# Remote.net
KiCad netlist of a schematic drawn in EAGLE
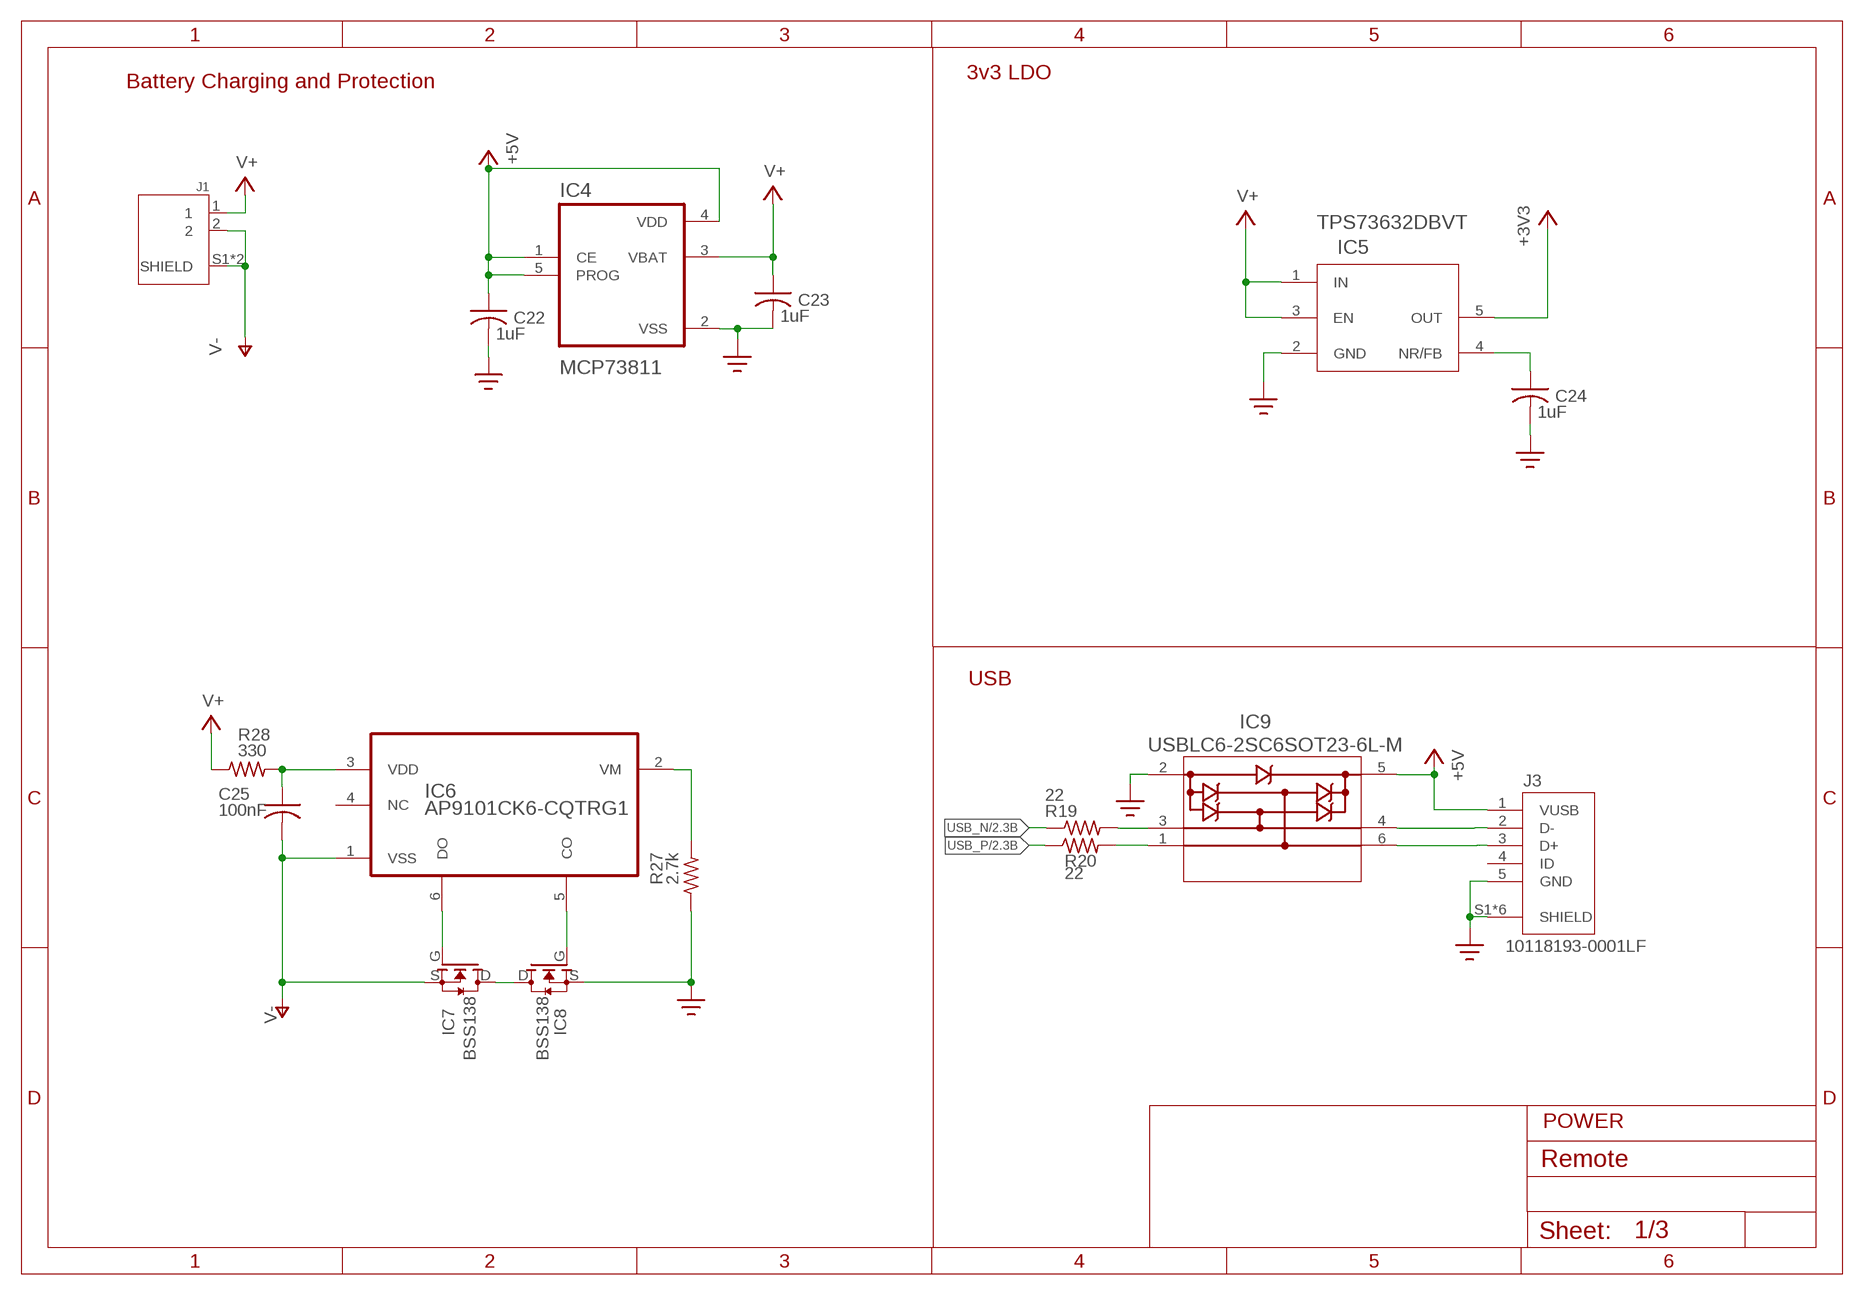
[diagram p0: schematic, sheet 1]
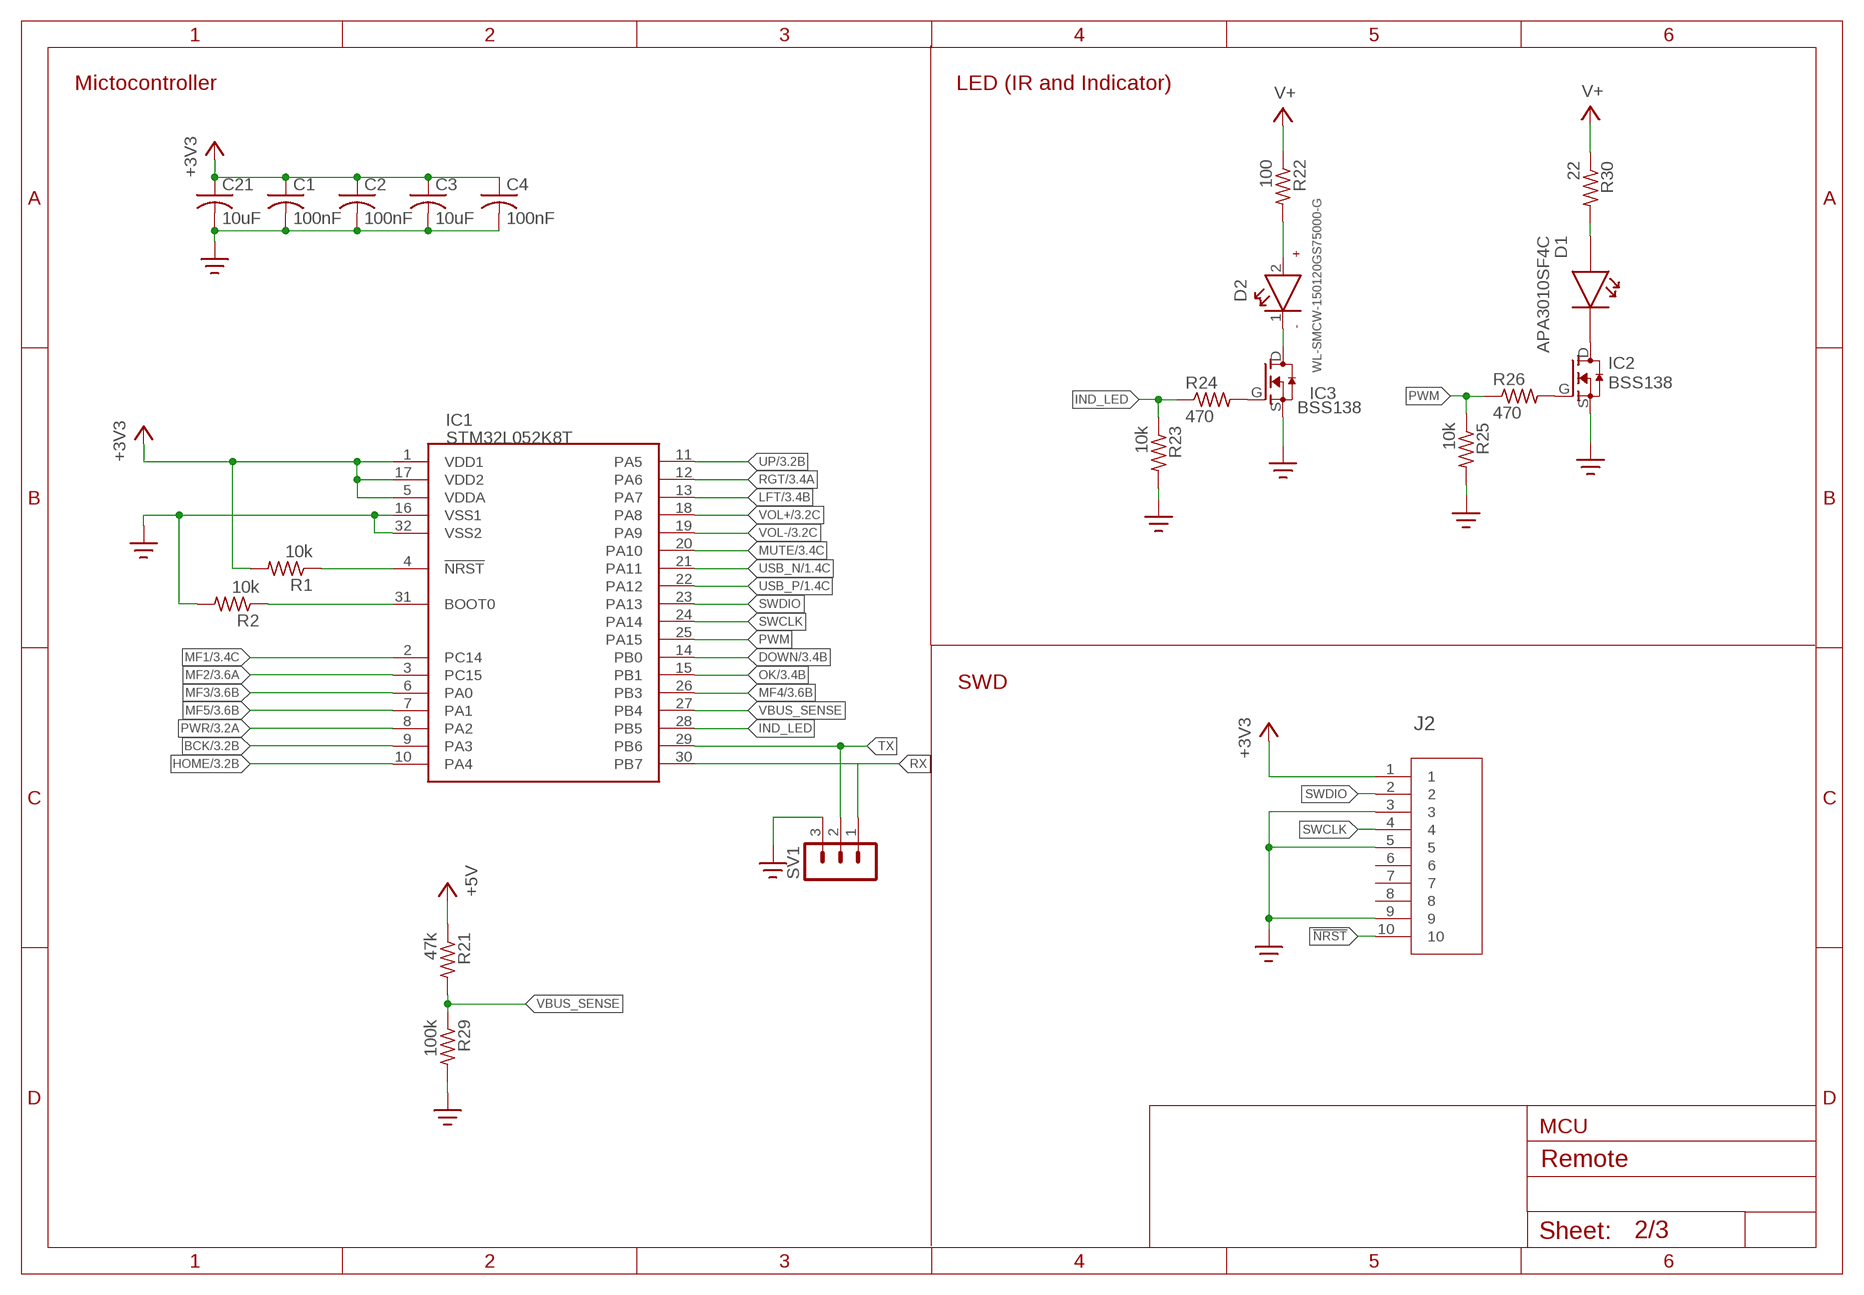
[diagram p1: schematic, sheet 2]
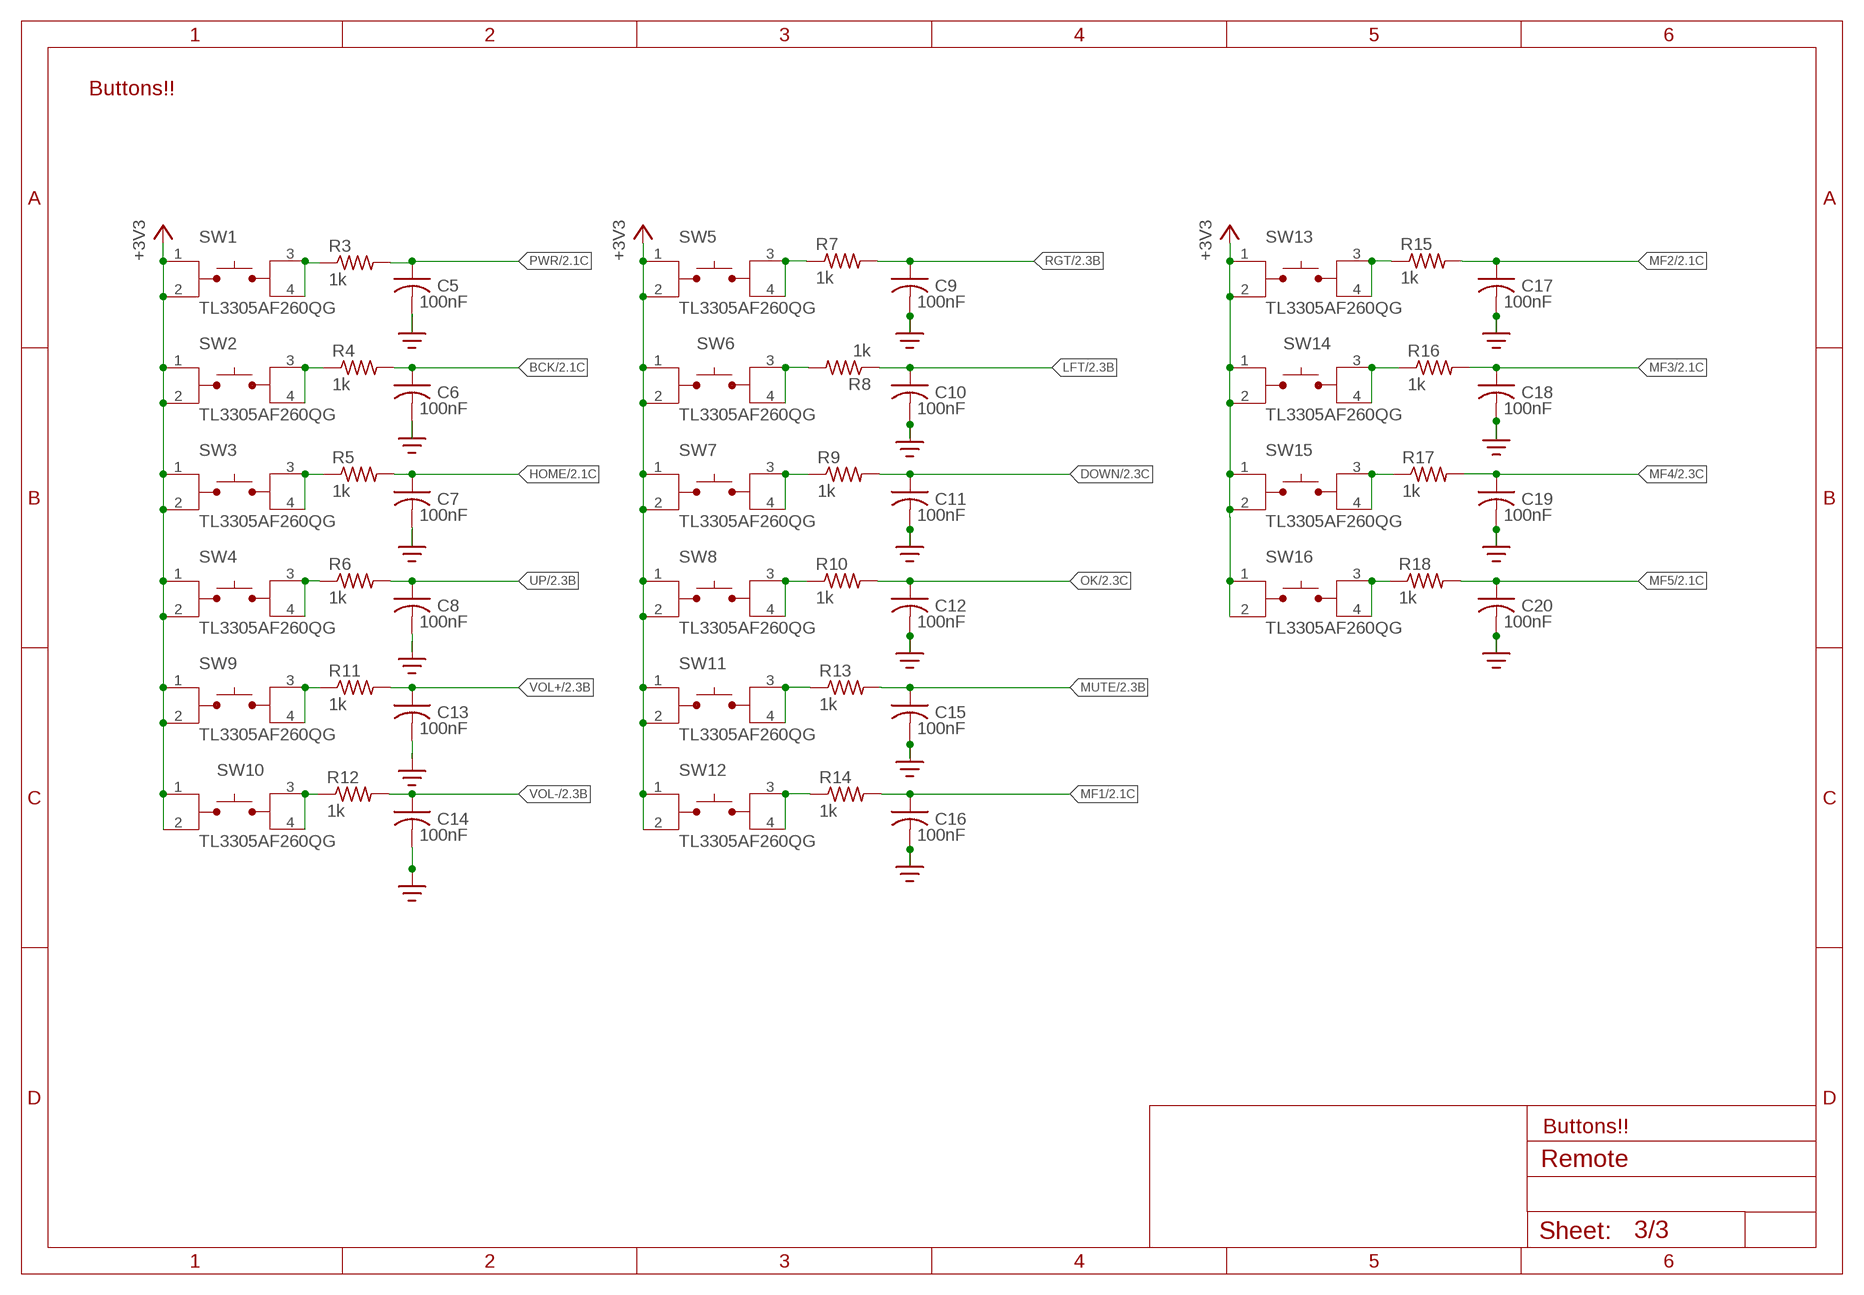
[diagram p2: schematic, sheet 3]

(export (version "E")
  (design (tool "Eeschema 10.0.6"))
  (components
    (comp (ref "C5")
      (value "100nF")
      (footprint "eagle-import:C0805K")
      (libsource (lib "eagle-import") (part "C-USC0805K"))
    )
    (comp (ref "C6")
      (value "100nF")
      (footprint "eagle-import:C0805K")
      (libsource (lib "eagle-import") (part "C-USC0805K"))
    )
    (comp (ref "C7")
      (value "100nF")
      (footprint "eagle-import:C0805K")
      (libsource (lib "eagle-import") (part "C-USC0805K"))
    )
    (comp (ref "C8")
      (value "100nF")
      (footprint "eagle-import:C0805K")
      (libsource (lib "eagle-import") (part "C-USC0805K"))
    )
    (comp (ref "C9")
      (value "100nF")
      (footprint "eagle-import:C0805K")
      (libsource (lib "eagle-import") (part "C-USC0805K"))
    )
    (comp (ref "C10")
      (value "100nF")
      (footprint "eagle-import:C0805K")
      (libsource (lib "eagle-import") (part "C-USC0805K"))
    )
    (comp (ref "C11")
      (value "100nF")
      (footprint "eagle-import:C0805K")
      (libsource (lib "eagle-import") (part "C-USC0805K"))
    )
    (comp (ref "C12")
      (value "100nF")
      (footprint "eagle-import:C0805K")
      (libsource (lib "eagle-import") (part "C-USC0805K"))
    )
    (comp (ref "C13")
      (value "100nF")
      (footprint "eagle-import:C0805K")
      (libsource (lib "eagle-import") (part "C-USC0805K"))
    )
    (comp (ref "C14")
      (value "100nF")
      (footprint "eagle-import:C0805K")
      (libsource (lib "eagle-import") (part "C-USC0805K"))
    )
    (comp (ref "C15")
      (value "100nF")
      (footprint "eagle-import:C0805K")
      (libsource (lib "eagle-import") (part "C-USC0805K"))
    )
    (comp (ref "C16")
      (value "100nF")
      (footprint "eagle-import:C0805K")
      (libsource (lib "eagle-import") (part "C-USC0805K"))
    )
    (comp (ref "C17")
      (value "100nF")
      (footprint "eagle-import:C0805K")
      (libsource (lib "eagle-import") (part "C-USC0805K"))
    )
    (comp (ref "C18")
      (value "100nF")
      (footprint "eagle-import:C0805K")
      (libsource (lib "eagle-import") (part "C-USC0805K"))
    )
    (comp (ref "C19")
      (value "100nF")
      (footprint "eagle-import:C0805K")
      (libsource (lib "eagle-import") (part "C-USC0805K"))
    )
    (comp (ref "C20")
      (value "100nF")
      (footprint "eagle-import:C0805K")
      (libsource (lib "eagle-import") (part "C-USC0805K"))
    )
    (comp (ref "R3")
      (value "1k")
      (footprint "eagle-import:R0805W")
      (libsource (lib "eagle-import") (part "R-US_R0805W"))
    )
    (comp (ref "R4")
      (value "1k")
      (footprint "eagle-import:R0805W")
      (libsource (lib "eagle-import") (part "R-US_R0805W"))
    )
    (comp (ref "R5")
      (value "1k")
      (footprint "eagle-import:R0805W")
      (libsource (lib "eagle-import") (part "R-US_R0805W"))
    )
    (comp (ref "R6")
      (value "1k")
      (footprint "eagle-import:R0805W")
      (libsource (lib "eagle-import") (part "R-US_R0805W"))
    )
    (comp (ref "R7")
      (value "1k")
      (footprint "eagle-import:R0805W")
      (libsource (lib "eagle-import") (part "R-US_R0805W"))
    )
    (comp (ref "R8")
      (value "1k")
      (footprint "eagle-import:R0805W")
      (libsource (lib "eagle-import") (part "R-US_R0805W"))
    )
    (comp (ref "R9")
      (value "1k")
      (footprint "eagle-import:R0805W")
      (libsource (lib "eagle-import") (part "R-US_R0805W"))
    )
    (comp (ref "R10")
      (value "1k")
      (footprint "eagle-import:R0805W")
      (libsource (lib "eagle-import") (part "R-US_R0805W"))
    )
    (comp (ref "R11")
      (value "1k")
      (footprint "eagle-import:R0805W")
      (libsource (lib "eagle-import") (part "R-US_R0805W"))
    )
    (comp (ref "R12")
      (value "1k")
      (footprint "eagle-import:R0805W")
      (libsource (lib "eagle-import") (part "R-US_R0805W"))
    )
    (comp (ref "R13")
      (value "1k")
      (footprint "eagle-import:R0805W")
      (libsource (lib "eagle-import") (part "R-US_R0805W"))
    )
    (comp (ref "R14")
      (value "1k")
      (footprint "eagle-import:R0805W")
      (libsource (lib "eagle-import") (part "R-US_R0805W"))
    )
    (comp (ref "R15")
      (value "1k")
      (footprint "eagle-import:R0805W")
      (libsource (lib "eagle-import") (part "R-US_R0805W"))
    )
    (comp (ref "R16")
      (value "1k")
      (footprint "eagle-import:R0805W")
      (libsource (lib "eagle-import") (part "R-US_R0805W"))
    )
    (comp (ref "R17")
      (value "1k")
      (footprint "eagle-import:R0805W")
      (libsource (lib "eagle-import") (part "R-US_R0805W"))
    )
    (comp (ref "R18")
      (value "1k")
      (footprint "eagle-import:R0805W")
      (libsource (lib "eagle-import") (part "R-US_R0805W"))
    )
    (comp (ref "SW1")
      (value "TL3305AF260QG")
      (footprint "eagle-import:SW_TL3305AF260QG")
      (fields (field (name "DIGI-KEY_PART_NUMBER") "EG5353CT-ND") (field (name "MF") "E-Switch"))
      (libsource (lib "eagle-import") (part "TL3305AF260QG"))
    )
    (comp (ref "SW2")
      (value "TL3305AF260QG")
      (footprint "eagle-import:SW_TL3305AF260QG")
      (fields (field (name "DIGI-KEY_PART_NUMBER") "EG5353CT-ND") (field (name "MF") "E-Switch"))
      (libsource (lib "eagle-import") (part "TL3305AF260QG"))
    )
    (comp (ref "SW3")
      (value "TL3305AF260QG")
      (footprint "eagle-import:SW_TL3305AF260QG")
      (fields (field (name "DIGI-KEY_PART_NUMBER") "EG5353CT-ND") (field (name "MF") "E-Switch"))
      (libsource (lib "eagle-import") (part "TL3305AF260QG"))
    )
    (comp (ref "SW4")
      (value "TL3305AF260QG")
      (footprint "eagle-import:SW_TL3305AF260QG")
      (fields (field (name "DIGI-KEY_PART_NUMBER") "EG5353CT-ND") (field (name "MF") "E-Switch"))
      (libsource (lib "eagle-import") (part "TL3305AF260QG"))
    )
    (comp (ref "SW5")
      (value "TL3305AF260QG")
      (footprint "eagle-import:SW_TL3305AF260QG")
      (fields (field (name "DIGI-KEY_PART_NUMBER") "EG5353CT-ND") (field (name "MF") "E-Switch"))
      (libsource (lib "eagle-import") (part "TL3305AF260QG"))
    )
    (comp (ref "SW6")
      (value "TL3305AF260QG")
      (footprint "eagle-import:SW_TL3305AF260QG")
      (fields (field (name "DIGI-KEY_PART_NUMBER") "EG5353CT-ND") (field (name "MF") "E-Switch"))
      (libsource (lib "eagle-import") (part "TL3305AF260QG"))
    )
    (comp (ref "SW7")
      (value "TL3305AF260QG")
      (footprint "eagle-import:SW_TL3305AF260QG")
      (fields (field (name "DIGI-KEY_PART_NUMBER") "EG5353CT-ND") (field (name "MF") "E-Switch"))
      (libsource (lib "eagle-import") (part "TL3305AF260QG"))
    )
    (comp (ref "SW8")
      (value "TL3305AF260QG")
      (footprint "eagle-import:SW_TL3305AF260QG")
      (fields (field (name "DIGI-KEY_PART_NUMBER") "EG5353CT-ND") (field (name "MF") "E-Switch"))
      (libsource (lib "eagle-import") (part "TL3305AF260QG"))
    )
    (comp (ref "SW9")
      (value "TL3305AF260QG")
      (footprint "eagle-import:SW_TL3305AF260QG")
      (fields (field (name "DIGI-KEY_PART_NUMBER") "EG5353CT-ND") (field (name "MF") "E-Switch"))
      (libsource (lib "eagle-import") (part "TL3305AF260QG"))
    )
    (comp (ref "SW10")
      (value "TL3305AF260QG")
      (footprint "eagle-import:SW_TL3305AF260QG")
      (fields (field (name "DIGI-KEY_PART_NUMBER") "EG5353CT-ND") (field (name "MF") "E-Switch"))
      (libsource (lib "eagle-import") (part "TL3305AF260QG"))
    )
    (comp (ref "SW11")
      (value "TL3305AF260QG")
      (footprint "eagle-import:SW_TL3305AF260QG")
      (fields (field (name "DIGI-KEY_PART_NUMBER") "EG5353CT-ND") (field (name "MF") "E-Switch"))
      (libsource (lib "eagle-import") (part "TL3305AF260QG"))
    )
    (comp (ref "SW12")
      (value "TL3305AF260QG")
      (footprint "eagle-import:SW_TL3305AF260QG")
      (fields (field (name "DIGI-KEY_PART_NUMBER") "EG5353CT-ND") (field (name "MF") "E-Switch"))
      (libsource (lib "eagle-import") (part "TL3305AF260QG"))
    )
    (comp (ref "SW13")
      (value "TL3305AF260QG")
      (footprint "eagle-import:SW_TL3305AF260QG")
      (fields (field (name "DIGI-KEY_PART_NUMBER") "EG5353CT-ND") (field (name "MF") "E-Switch"))
      (libsource (lib "eagle-import") (part "TL3305AF260QG"))
    )
    (comp (ref "SW14")
      (value "TL3305AF260QG")
      (footprint "eagle-import:SW_TL3305AF260QG")
      (fields (field (name "DIGI-KEY_PART_NUMBER") "EG5353CT-ND") (field (name "MF") "E-Switch"))
      (libsource (lib "eagle-import") (part "TL3305AF260QG"))
    )
    (comp (ref "SW15")
      (value "TL3305AF260QG")
      (footprint "eagle-import:SW_TL3305AF260QG")
      (fields (field (name "DIGI-KEY_PART_NUMBER") "EG5353CT-ND") (field (name "MF") "E-Switch"))
      (libsource (lib "eagle-import") (part "TL3305AF260QG"))
    )
    (comp (ref "SW16")
      (value "TL3305AF260QG")
      (footprint "eagle-import:SW_TL3305AF260QG")
      (fields (field (name "DIGI-KEY_PART_NUMBER") "EG5353CT-ND") (field (name "MF") "E-Switch"))
      (libsource (lib "eagle-import") (part "TL3305AF260QG"))
    )
    (comp (ref "C1")
      (value "100nF")
      (footprint "eagle-import:C0805K")
      (libsource (lib "eagle-import") (part "C-USC0805K"))
    )
    (comp (ref "C2")
      (value "100nF")
      (footprint "eagle-import:C0805K")
      (libsource (lib "eagle-import") (part "C-USC0805K"))
    )
    (comp (ref "C3")
      (value "10uF")
      (footprint "eagle-import:C0805K")
      (libsource (lib "eagle-import") (part "C-USC0805K"))
    )
    (comp (ref "C4")
      (value "100nF")
      (footprint "eagle-import:C0805K")
      (libsource (lib "eagle-import") (part "C-USC0805K"))
    )
    (comp (ref "C21")
      (value "10uF")
      (footprint "eagle-import:C0805K")
      (libsource (lib "eagle-import") (part "C-USC0805K"))
    )
    (comp (ref "D1")
      (value "APA3010SF4C")
      (footprint "eagle-import:APA3010SF4C")
      (fields (field (name "DIGI-KEY_PART_NUMBER") "754-1070-1-ND") (field (name "MF") "Kingbright"))
      (libsource (lib "eagle-import") (part "APA3010SF4C"))
    )
    (comp (ref "D2")
      (value "WL-SMCW-150120GS75000-G")
      (footprint "eagle-import:WL-SMCW_1206")
      (fields (field (name "MF") "Wurth Electronics") (field (name "MP") "150060VS75000"))
      (libsource (lib "eagle-import") (part "WL-SMCW-150120GS75000-G"))
    )
    (comp (ref "IC1")
      (value "STM32L052K8T")
      (footprint "eagle-import:QFP80P900X900X160-32N")
      (libsource (lib "eagle-import") (part "STM32L052K8T"))
    )
    (comp (ref "IC2")
      (value "BSS138")
      (footprint "eagle-import:BSS138")
      (fields (field (name "MF") "MICROSS/On Semiconductor"))
      (libsource (lib "eagle-import") (part "BSS138"))
    )
    (comp (ref "IC3")
      (value "BSS138")
      (footprint "eagle-import:BSS138")
      (fields (field (name "MF") "MICROSS/On Semiconductor"))
      (libsource (lib "eagle-import") (part "BSS138"))
    )
    (comp (ref "J2")
      (value "20021121-00010C4LF")
      (footprint "eagle-import:CONN_00010C4LF_AMP")
      (fields (field (name "COPYRIGHT") "Copyright (C) 2018 Accelerated Designs. All rights reserved"))
      (libsource (lib "eagle-import") (part "20021121-00010C4LF"))
    )
    (comp (ref "R1")
      (value "10k")
      (footprint "eagle-import:R0805W")
      (libsource (lib "eagle-import") (part "R-US_R0805W"))
    )
    (comp (ref "R2")
      (value "10k")
      (footprint "eagle-import:R0805W")
      (libsource (lib "eagle-import") (part "R-US_R0805W"))
    )
    (comp (ref "R21")
      (value "47k")
      (footprint "eagle-import:R0805W")
      (libsource (lib "eagle-import") (part "R-US_R0805W"))
    )
    (comp (ref "R22")
      (value "100")
      (footprint "eagle-import:R0805W")
      (libsource (lib "eagle-import") (part "R-US_R0805W"))
    )
    (comp (ref "R23")
      (value "10k")
      (footprint "eagle-import:R0805W")
      (libsource (lib "eagle-import") (part "R-US_R0805W"))
    )
    (comp (ref "R24")
      (value "470")
      (footprint "eagle-import:R0805W")
      (libsource (lib "eagle-import") (part "R-US_R0805W"))
    )
    (comp (ref "R25")
      (value "10k")
      (footprint "eagle-import:R0805W")
      (libsource (lib "eagle-import") (part "R-US_R0805W"))
    )
    (comp (ref "R26")
      (value "470")
      (footprint "eagle-import:R0805W")
      (libsource (lib "eagle-import") (part "R-US_R0805W"))
    )
    (comp (ref "R29")
      (value "100k")
      (footprint "eagle-import:R0805W")
      (libsource (lib "eagle-import") (part "R-US_R0805W"))
    )
    (comp (ref "R30")
      (value "22")
      (footprint "eagle-import:R0805W")
      (libsource (lib "eagle-import") (part "R-US_R0805W"))
    )
    (comp (ref "SV1")
      (value "MA03-1")
      (footprint "eagle-import:MA03-1")
      (libsource (lib "eagle-import") (part "MA03-1"))
    )
    (comp (ref "C22")
      (value "1uF")
      (footprint "eagle-import:C0805K")
      (libsource (lib "eagle-import") (part "C-USC0805K"))
    )
    (comp (ref "C23")
      (value "1uF")
      (footprint "eagle-import:C0805K")
      (libsource (lib "eagle-import") (part "C-USC0805K"))
    )
    (comp (ref "C24")
      (value "1uF")
      (footprint "eagle-import:C0805K")
      (libsource (lib "eagle-import") (part "C-USC0805K"))
    )
    (comp (ref "C25")
      (value "100nF")
      (footprint "eagle-import:C0805K")
      (libsource (lib "eagle-import") (part "C-USC0805K"))
    )
    (comp (ref "IC4")
      (value "MCP73811")
      (footprint "eagle-import:SOT95P280X145-5N")
      (fields
        (field (name "DIGI-KEY_PART_NUMBER") "MCP73811T-420I/OTCT-ND")
        (field (name "MF") "Microchip")
        (field (name "MP") "MCP73811T-420I/OT")
      )
      (libsource (lib "eagle-import") (part "MCP73811T-420I/OT"))
    )
    (comp (ref "IC5")
      (value "TPS73632DBVT")
      (footprint "eagle-import:DBV5-M")
      (fields (field (name "MANUFACTURER") "Texas Instruments"))
      (libsource (lib "eagle-import") (part "TPS73632DBVTDBV5-M"))
    )
    (comp (ref "IC6")
      (value "AP9101CK6-CQTRG1")
      (footprint "eagle-import:SOT95P280X140-6N")
      (fields (field (name "MF") "Diodes Inc."))
      (libsource (lib "eagle-import") (part "AP9101CK6-CQTRG1"))
    )
    (comp (ref "IC7")
      (value "BSS138")
      (footprint "eagle-import:BSS138")
      (fields (field (name "MF") "MICROSS/On Semiconductor"))
      (libsource (lib "eagle-import") (part "BSS138"))
    )
    (comp (ref "IC8")
      (value "BSS138")
      (footprint "eagle-import:BSS138")
      (fields (field (name "MF") "MICROSS/On Semiconductor"))
      (libsource (lib "eagle-import") (part "BSS138"))
    )
    (comp (ref "IC9")
      (value "USBLC6-2SC6SOT23-6L-M")
      (footprint "eagle-import:SOT23-6L-M")
      (fields (field (name "MANUFACTURER_PART_NUMBER") "USBLC6-2SC6"))
      (libsource (lib "eagle-import") (part "USBLC6-2SC6SOT23-6L-M"))
    )
    (comp (ref "J1")
      (value "S2B-PH-SM4-TB(LF)(SN)")
      (footprint "eagle-import:JST_S2B-PH-SM4-TB(LF)(SN)")
      (fields (field (name "MF") "JST Sales") (field (name "MP") "S2B-PH-SM4-TB_LF__SN_"))
      (libsource (lib "eagle-import") (part "S2B-PH-SM4-TB(LF)(SN)"))
    )
    (comp (ref "J3")
      (value "10118193-0001LF")
      (footprint "eagle-import:FCI_10118193-0001LF")
      (fields (field (name "DIGI-KEY_PART_NUMBER") "609-4616-1-ND") (field (name "MF") "Amphenol ICC"))
      (libsource (lib "eagle-import") (part "10118193-0001LF"))
    )
    (comp (ref "R19")
      (value "22")
      (footprint "eagle-import:R0805W")
      (libsource (lib "eagle-import") (part "R-US_R0805W"))
    )
    (comp (ref "R20")
      (value "22")
      (footprint "eagle-import:R0805W")
      (libsource (lib "eagle-import") (part "R-US_R0805W"))
    )
    (comp (ref "R27")
      (value "2.7k")
      (footprint "eagle-import:R0805W")
      (libsource (lib "eagle-import") (part "R-US_R0805W"))
    )
    (comp (ref "R28")
      (value "330")
      (footprint "eagle-import:R0805W")
      (libsource (lib "eagle-import") (part "R-US_R0805W"))
    )
  )
  (nets
    (net (code "1") (name "+3V3") (class "Default")
      (node (ref "C1") (pin "1") (pinfunction "1_1") (pintype "passive"))
      (node (ref "C2") (pin "1") (pinfunction "1_1") (pintype "passive"))
      (node (ref "C21") (pin "1") (pinfunction "1_1") (pintype "passive"))
      (node (ref "C3") (pin "1") (pinfunction "1_1") (pintype "passive"))
      (node (ref "C4") (pin "1") (pinfunction "1_1") (pintype "passive"))
      (node (ref "IC1") (pin "1") (pinfunction "VDD1_1") (pintype "power_in"))
      (node (ref "IC1") (pin "17") (pinfunction "VDD2_17") (pintype "power_in"))
      (node (ref "IC1") (pin "5") (pinfunction "VDDA_5") (pintype "power_in"))
      (node (ref "IC5") (pin "5") (pinfunction "OUT_5") (pintype "output"))
      (node (ref "J2") (pin "1") (pinfunction "1_1") (pintype "passive"))
      (node (ref "R1") (pin "2") (pinfunction "2_2") (pintype "passive"))
      (node (ref "SW1") (pin "1") (pinfunction "1_1") (pintype "passive"))
      (node (ref "SW1") (pin "2") (pinfunction "2_2") (pintype "passive"))
      (node (ref "SW10") (pin "1") (pinfunction "1_1") (pintype "passive"))
      (node (ref "SW10") (pin "2") (pinfunction "2_2") (pintype "passive"))
      (node (ref "SW11") (pin "1") (pinfunction "1_1") (pintype "passive"))
      (node (ref "SW11") (pin "2") (pinfunction "2_2") (pintype "passive"))
      (node (ref "SW12") (pin "1") (pinfunction "1_1") (pintype "passive"))
      (node (ref "SW12") (pin "2") (pinfunction "2_2") (pintype "passive"))
      (node (ref "SW13") (pin "1") (pinfunction "1_1") (pintype "passive"))
      (node (ref "SW13") (pin "2") (pinfunction "2_2") (pintype "passive"))
      (node (ref "SW14") (pin "1") (pinfunction "1_1") (pintype "passive"))
      (node (ref "SW14") (pin "2") (pinfunction "2_2") (pintype "passive"))
      (node (ref "SW15") (pin "1") (pinfunction "1_1") (pintype "passive"))
      (node (ref "SW15") (pin "2") (pinfunction "2_2") (pintype "passive"))
      (node (ref "SW16") (pin "1") (pinfunction "1_1") (pintype "passive"))
      (node (ref "SW16") (pin "2") (pinfunction "2_2") (pintype "passive"))
      (node (ref "SW2") (pin "1") (pinfunction "1_1") (pintype "passive"))
      (node (ref "SW2") (pin "2") (pinfunction "2_2") (pintype "passive"))
      (node (ref "SW3") (pin "1") (pinfunction "1_1") (pintype "passive"))
      (node (ref "SW3") (pin "2") (pinfunction "2_2") (pintype "passive"))
      (node (ref "SW4") (pin "1") (pinfunction "1_1") (pintype "passive"))
      (node (ref "SW4") (pin "2") (pinfunction "2_2") (pintype "passive"))
      (node (ref "SW5") (pin "1") (pinfunction "1_1") (pintype "passive"))
      (node (ref "SW5") (pin "2") (pinfunction "2_2") (pintype "passive"))
      (node (ref "SW6") (pin "1") (pinfunction "1_1") (pintype "passive"))
      (node (ref "SW6") (pin "2") (pinfunction "2_2") (pintype "passive"))
      (node (ref "SW7") (pin "1") (pinfunction "1_1") (pintype "passive"))
      (node (ref "SW7") (pin "2") (pinfunction "2_2") (pintype "passive"))
      (node (ref "SW8") (pin "1") (pinfunction "1_1") (pintype "passive"))
      (node (ref "SW8") (pin "2") (pinfunction "2_2") (pintype "passive"))
      (node (ref "SW9") (pin "1") (pinfunction "1_1") (pintype "passive"))
      (node (ref "SW9") (pin "2") (pinfunction "2_2") (pintype "passive"))
    )
    (net (code "2") (name "+5V") (class "Default")
      (node (ref "C22") (pin "1") (pinfunction "1_1") (pintype "passive"))
      (node (ref "IC4") (pin "1") (pinfunction "CE_1") (pintype "input"))
      (node (ref "IC4") (pin "4") (pinfunction "VDD_4") (pintype "power_in"))
      (node (ref "IC4") (pin "5") (pinfunction "PROG_5") (pintype "input"))
      (node (ref "IC9") (pin "5") (pinfunction "VBUS_5") (pintype "power_in"))
      (node (ref "J3") (pin "1") (pinfunction "VUSB_1") (pintype "passive"))
      (node (ref "R21") (pin "1") (pinfunction "1_1") (pintype "passive"))
    )
    (net (code "3") (name "BCK") (class "Default")
      (node (ref "C6") (pin "1") (pinfunction "1_1") (pintype "passive"))
      (node (ref "IC1") (pin "9") (pinfunction "PA3_9") (pintype "bidirectional"))
      (node (ref "R4") (pin "2") (pinfunction "2_2") (pintype "passive"))
    )
    (net (code "4") (name "DOWN") (class "Default")
      (node (ref "C11") (pin "1") (pinfunction "1_1") (pintype "passive"))
      (node (ref "IC1") (pin "14") (pinfunction "PB0_14") (pintype "bidirectional"))
      (node (ref "R9") (pin "2") (pinfunction "2_2") (pintype "passive"))
    )
    (net (code "5") (name "GND") (class "Default")
      (node (ref "C1") (pin "2") (pinfunction "2_2") (pintype "passive"))
      (node (ref "C10") (pin "2") (pinfunction "2_2") (pintype "passive"))
      (node (ref "C11") (pin "2") (pinfunction "2_2") (pintype "passive"))
      (node (ref "C12") (pin "2") (pinfunction "2_2") (pintype "passive"))
      (node (ref "C13") (pin "2") (pinfunction "2_2") (pintype "passive"))
      (node (ref "C14") (pin "2") (pinfunction "2_2") (pintype "passive"))
      (node (ref "C15") (pin "2") (pinfunction "2_2") (pintype "passive"))
      (node (ref "C16") (pin "2") (pinfunction "2_2") (pintype "passive"))
      (node (ref "C17") (pin "2") (pinfunction "2_2") (pintype "passive"))
      (node (ref "C18") (pin "2") (pinfunction "2_2") (pintype "passive"))
      (node (ref "C19") (pin "2") (pinfunction "2_2") (pintype "passive"))
      (node (ref "C2") (pin "2") (pinfunction "2_2") (pintype "passive"))
      (node (ref "C20") (pin "2") (pinfunction "2_2") (pintype "passive"))
      (node (ref "C21") (pin "2") (pinfunction "2_2") (pintype "passive"))
      (node (ref "C22") (pin "2") (pinfunction "2_2") (pintype "passive"))
      (node (ref "C23") (pin "2") (pinfunction "2_2") (pintype "passive"))
      (node (ref "C24") (pin "2") (pinfunction "2_2") (pintype "passive"))
      (node (ref "C3") (pin "2") (pinfunction "2_2") (pintype "passive"))
      (node (ref "C4") (pin "2") (pinfunction "2_2") (pintype "passive"))
      (node (ref "C5") (pin "2") (pinfunction "2_2") (pintype "passive"))
      (node (ref "C6") (pin "2") (pinfunction "2_2") (pintype "passive"))
      (node (ref "C7") (pin "2") (pinfunction "2_2") (pintype "passive"))
      (node (ref "C8") (pin "2") (pinfunction "2_2") (pintype "passive"))
      (node (ref "C9") (pin "2") (pinfunction "2_2") (pintype "passive"))
      (node (ref "IC1") (pin "16") (pinfunction "VSS1_16") (pintype "power_in"))
      (node (ref "IC1") (pin "32") (pinfunction "VSS2_32") (pintype "power_in"))
      (node (ref "IC2") (pin "S") (pinfunction "S_S") (pintype "passive"))
      (node (ref "IC3") (pin "S") (pinfunction "S_S") (pintype "passive"))
      (node (ref "IC4") (pin "2") (pinfunction "VSS_2") (pintype "power_in"))
      (node (ref "IC5") (pin "2") (pinfunction "GND_2") (pintype "power_in"))
      (node (ref "IC8") (pin "S") (pinfunction "S_S") (pintype "passive"))
      (node (ref "IC9") (pin "2") (pinfunction "GND_2") (pintype "power_in"))
      (node (ref "J2") (pin "3") (pinfunction "3_3") (pintype "passive"))
      (node (ref "J2") (pin "5") (pinfunction "5_5") (pintype "passive"))
      (node (ref "J2") (pin "9") (pinfunction "9_9") (pintype "passive"))
      (node (ref "J3") (pin "5") (pinfunction "GND_5") (pintype "passive"))
      (node (ref "J3") (pin "S1") (pinfunction "SHIELD_S1") (pintype "passive"))
      (node (ref "J3") (pin "S2") (pinfunction "SHIELD_S2") (pintype "passive"))
      (node (ref "J3") (pin "S3") (pinfunction "SHIELD_S3") (pintype "passive"))
      (node (ref "J3") (pin "S4") (pinfunction "SHIELD_S4") (pintype "passive"))
      (node (ref "J3") (pin "S5") (pinfunction "SHIELD_S5") (pintype "passive"))
      (node (ref "J3") (pin "S6") (pinfunction "SHIELD_S6") (pintype "passive"))
      (node (ref "R2") (pin "2") (pinfunction "2_2") (pintype "passive"))
      (node (ref "R23") (pin "2") (pinfunction "2_2") (pintype "passive"))
      (node (ref "R25") (pin "2") (pinfunction "2_2") (pintype "passive"))
      (node (ref "R27") (pin "1") (pinfunction "1_1") (pintype "passive"))
      (node (ref "R29") (pin "2") (pinfunction "2_2") (pintype "passive"))
      (node (ref "SV1") (pin "3") (pinfunction "3_3") (pintype "passive"))
    )
    (net (code "6") (name "HOME") (class "Default")
      (node (ref "C7") (pin "1") (pinfunction "1_1") (pintype "passive"))
      (node (ref "IC1") (pin "10") (pinfunction "PA4_10") (pintype "bidirectional"))
      (node (ref "R5") (pin "2") (pinfunction "2_2") (pintype "passive"))
    )
    (net (code "7") (name "IND_LED") (class "Default")
      (node (ref "IC1") (pin "28") (pinfunction "PB5_28") (pintype "bidirectional"))
      (node (ref "R23") (pin "1") (pinfunction "1_1") (pintype "passive"))
      (node (ref "R24") (pin "1") (pinfunction "1_1") (pintype "passive"))
    )
    (net (code "8") (name "LFT") (class "Default")
      (node (ref "C10") (pin "1") (pinfunction "1_1") (pintype "passive"))
      (node (ref "IC1") (pin "13") (pinfunction "PA7_13") (pintype "bidirectional"))
      (node (ref "R8") (pin "1") (pinfunction "1_1") (pintype "passive"))
    )
    (net (code "9") (name "MF1") (class "Default")
      (node (ref "C16") (pin "1") (pinfunction "1_1") (pintype "passive"))
      (node (ref "IC1") (pin "2") (pinfunction "PC14_2") (pintype "bidirectional"))
      (node (ref "R14") (pin "2") (pinfunction "2_2") (pintype "passive"))
    )
    (net (code "10") (name "MF2") (class "Default")
      (node (ref "C17") (pin "1") (pinfunction "1_1") (pintype "passive"))
      (node (ref "IC1") (pin "3") (pinfunction "PC15_3") (pintype "bidirectional"))
      (node (ref "R15") (pin "2") (pinfunction "2_2") (pintype "passive"))
    )
    (net (code "11") (name "MF3") (class "Default")
      (node (ref "C18") (pin "1") (pinfunction "1_1") (pintype "passive"))
      (node (ref "IC1") (pin "6") (pinfunction "PA0_6") (pintype "bidirectional"))
      (node (ref "R16") (pin "2") (pinfunction "2_2") (pintype "passive"))
    )
    (net (code "12") (name "MF4") (class "Default")
      (node (ref "C19") (pin "1") (pinfunction "1_1") (pintype "passive"))
      (node (ref "IC1") (pin "26") (pinfunction "PB3_26") (pintype "bidirectional"))
      (node (ref "R17") (pin "2") (pinfunction "2_2") (pintype "passive"))
    )
    (net (code "13") (name "MF5") (class "Default")
      (node (ref "C20") (pin "1") (pinfunction "1_1") (pintype "passive"))
      (node (ref "IC1") (pin "7") (pinfunction "PA1_7") (pintype "bidirectional"))
      (node (ref "R18") (pin "2") (pinfunction "2_2") (pintype "passive"))
    )
    (net (code "14") (name "MUTE") (class "Default")
      (node (ref "C15") (pin "1") (pinfunction "1_1") (pintype "passive"))
      (node (ref "IC1") (pin "20") (pinfunction "PA10_20") (pintype "bidirectional"))
      (node (ref "R13") (pin "2") (pinfunction "2_2") (pintype "passive"))
    )
    (net (code "15") (name "Net-(D1-Pad1)") (class "Default")
      (node (ref "D1") (pin "1") (pinfunction "1_1") (pintype "bidirectional"))
      (node (ref "R30") (pin "2") (pinfunction "2_2") (pintype "passive"))
    )
    (net (code "16") (name "Net-(D1-Pad2)") (class "Default")
      (node (ref "D1") (pin "2") (pinfunction "2_2") (pintype "bidirectional"))
      (node (ref "IC2") (pin "D") (pinfunction "D_D") (pintype "passive"))
    )
    (net (code "17") (name "Net-(D2-+)") (class "Default")
      (node (ref "D2") (pin "2") (pinfunction "+_2") (pintype "bidirectional"))
      (node (ref "R22") (pin "2") (pinfunction "2_2") (pintype "passive"))
    )
    (net (code "18") (name "Net-(D2--)") (class "Default")
      (node (ref "D2") (pin "1") (pinfunction "-_1") (pintype "bidirectional"))
      (node (ref "IC3") (pin "D") (pinfunction "D_D") (pintype "passive"))
    )
    (net (code "19") (name "Net-(IC1-BOOT0)") (class "Default")
      (node (ref "IC1") (pin "31") (pinfunction "BOOT0_31") (pintype "input"))
      (node (ref "R2") (pin "1") (pinfunction "1_1") (pintype "passive"))
    )
    (net (code "20") (name "Net-(IC2-PadG)") (class "Default")
      (node (ref "IC2") (pin "G") (pinfunction "G_G") (pintype "passive"))
      (node (ref "R26") (pin "2") (pinfunction "2_2") (pintype "passive"))
    )
    (net (code "21") (name "Net-(IC3-PadG)") (class "Default")
      (node (ref "IC3") (pin "G") (pinfunction "G_G") (pintype "passive"))
      (node (ref "R24") (pin "2") (pinfunction "2_2") (pintype "passive"))
    )
    (net (code "22") (name "Net-(IC5-NR{slash}FB)") (class "Default")
      (node (ref "C24") (pin "1") (pinfunction "1_1") (pintype "passive"))
      (node (ref "IC5") (pin "4") (pinfunction "NR/FB_4") (pintype "bidirectional"))
    )
    (net (code "23") (name "Net-(IC6-CO)") (class "Default")
      (node (ref "IC6") (pin "5") (pinfunction "CO_5") (pintype "input"))
      (node (ref "IC8") (pin "G") (pinfunction "G_G") (pintype "passive"))
    )
    (net (code "24") (name "Net-(IC6-DO)") (class "Default")
      (node (ref "IC6") (pin "6") (pinfunction "DO_6") (pintype "input"))
      (node (ref "IC7") (pin "G") (pinfunction "G_G") (pintype "passive"))
    )
    (net (code "25") (name "Net-(IC6-VDD)") (class "Default")
      (node (ref "C25") (pin "1") (pinfunction "1_1") (pintype "passive"))
      (node (ref "IC6") (pin "3") (pinfunction "VDD_3") (pintype "input"))
      (node (ref "R28") (pin "2") (pinfunction "2_2") (pintype "passive"))
    )
    (net (code "26") (name "Net-(IC6-VM)") (class "Default")
      (node (ref "IC6") (pin "2") (pinfunction "VM_2") (pintype "input"))
      (node (ref "R27") (pin "2") (pinfunction "2_2") (pintype "passive"))
    )
    (net (code "27") (name "Net-(IC7-PadD)") (class "Default")
      (node (ref "IC7") (pin "D") (pinfunction "D_D") (pintype "passive"))
      (node (ref "IC8") (pin "D") (pinfunction "D_D") (pintype "passive"))
    )
    (net (code "28") (name "Net-(IC9-I{slash}O1)") (class "Default")
      (node (ref "IC9") (pin "6") (pinfunction "I/O1_6") (pintype "bidirectional"))
      (node (ref "J3") (pin "3") (pinfunction "D+_3") (pintype "passive"))
    )
    (net (code "29") (name "Net-(IC9-I{slash}O1_2)") (class "Default")
      (node (ref "IC9") (pin "1") (pinfunction "I/O1_2_1") (pintype "bidirectional"))
      (node (ref "R20") (pin "2") (pinfunction "2_2") (pintype "passive"))
    )
    (net (code "30") (name "Net-(IC9-I{slash}O2)") (class "Default")
      (node (ref "IC9") (pin "4") (pinfunction "I/O2_4") (pintype "bidirectional"))
      (node (ref "J3") (pin "2") (pinfunction "D-_2") (pintype "passive"))
    )
    (net (code "31") (name "Net-(IC9-I{slash}O2_2)") (class "Default")
      (node (ref "IC9") (pin "3") (pinfunction "I/O2_2_3") (pintype "bidirectional"))
      (node (ref "R19") (pin "2") (pinfunction "2_2") (pintype "passive"))
    )
    (net (code "32") (name "Net-(R3-Pad1)") (class "Default")
      (node (ref "R3") (pin "1") (pinfunction "1_1") (pintype "passive"))
      (node (ref "SW1") (pin "3") (pinfunction "3_3") (pintype "passive"))
      (node (ref "SW1") (pin "4") (pinfunction "4_4") (pintype "passive"))
    )
    (net (code "33") (name "Net-(R4-Pad1)") (class "Default")
      (node (ref "R4") (pin "1") (pinfunction "1_1") (pintype "passive"))
      (node (ref "SW2") (pin "3") (pinfunction "3_3") (pintype "passive"))
      (node (ref "SW2") (pin "4") (pinfunction "4_4") (pintype "passive"))
    )
    (net (code "34") (name "Net-(R5-Pad1)") (class "Default")
      (node (ref "R5") (pin "1") (pinfunction "1_1") (pintype "passive"))
      (node (ref "SW3") (pin "3") (pinfunction "3_3") (pintype "passive"))
      (node (ref "SW3") (pin "4") (pinfunction "4_4") (pintype "passive"))
    )
    (net (code "35") (name "Net-(R6-Pad1)") (class "Default")
      (node (ref "R6") (pin "1") (pinfunction "1_1") (pintype "passive"))
      (node (ref "SW4") (pin "3") (pinfunction "3_3") (pintype "passive"))
      (node (ref "SW4") (pin "4") (pinfunction "4_4") (pintype "passive"))
    )
    (net (code "36") (name "Net-(R7-Pad1)") (class "Default")
      (node (ref "R7") (pin "1") (pinfunction "1_1") (pintype "passive"))
      (node (ref "SW5") (pin "3") (pinfunction "3_3") (pintype "passive"))
      (node (ref "SW5") (pin "4") (pinfunction "4_4") (pintype "passive"))
    )
    (net (code "37") (name "Net-(R8-Pad2)") (class "Default")
      (node (ref "R8") (pin "2") (pinfunction "2_2") (pintype "passive"))
      (node (ref "SW6") (pin "3") (pinfunction "3_3") (pintype "passive"))
      (node (ref "SW6") (pin "4") (pinfunction "4_4") (pintype "passive"))
    )
    (net (code "38") (name "Net-(R9-Pad1)") (class "Default")
      (node (ref "R9") (pin "1") (pinfunction "1_1") (pintype "passive"))
      (node (ref "SW7") (pin "3") (pinfunction "3_3") (pintype "passive"))
      (node (ref "SW7") (pin "4") (pinfunction "4_4") (pintype "passive"))
    )
    (net (code "39") (name "Net-(R10-Pad1)") (class "Default")
      (node (ref "R10") (pin "1") (pinfunction "1_1") (pintype "passive"))
      (node (ref "SW8") (pin "3") (pinfunction "3_3") (pintype "passive"))
      (node (ref "SW8") (pin "4") (pinfunction "4_4") (pintype "passive"))
    )
    (net (code "40") (name "Net-(R11-Pad1)") (class "Default")
      (node (ref "R11") (pin "1") (pinfunction "1_1") (pintype "passive"))
      (node (ref "SW9") (pin "3") (pinfunction "3_3") (pintype "passive"))
      (node (ref "SW9") (pin "4") (pinfunction "4_4") (pintype "passive"))
    )
    (net (code "41") (name "Net-(R12-Pad1)") (class "Default")
      (node (ref "R12") (pin "1") (pinfunction "1_1") (pintype "passive"))
      (node (ref "SW10") (pin "3") (pinfunction "3_3") (pintype "passive"))
      (node (ref "SW10") (pin "4") (pinfunction "4_4") (pintype "passive"))
    )
    (net (code "42") (name "Net-(R13-Pad1)") (class "Default")
      (node (ref "R13") (pin "1") (pinfunction "1_1") (pintype "passive"))
      (node (ref "SW11") (pin "3") (pinfunction "3_3") (pintype "passive"))
      (node (ref "SW11") (pin "4") (pinfunction "4_4") (pintype "passive"))
    )
    (net (code "43") (name "Net-(R14-Pad1)") (class "Default")
      (node (ref "R14") (pin "1") (pinfunction "1_1") (pintype "passive"))
      (node (ref "SW12") (pin "3") (pinfunction "3_3") (pintype "passive"))
      (node (ref "SW12") (pin "4") (pinfunction "4_4") (pintype "passive"))
    )
    (net (code "44") (name "Net-(R15-Pad1)") (class "Default")
      (node (ref "R15") (pin "1") (pinfunction "1_1") (pintype "passive"))
      (node (ref "SW13") (pin "3") (pinfunction "3_3") (pintype "passive"))
      (node (ref "SW13") (pin "4") (pinfunction "4_4") (pintype "passive"))
    )
    (net (code "45") (name "Net-(R16-Pad1)") (class "Default")
      (node (ref "R16") (pin "1") (pinfunction "1_1") (pintype "passive"))
      (node (ref "SW14") (pin "3") (pinfunction "3_3") (pintype "passive"))
      (node (ref "SW14") (pin "4") (pinfunction "4_4") (pintype "passive"))
    )
    (net (code "46") (name "Net-(R17-Pad1)") (class "Default")
      (node (ref "R17") (pin "1") (pinfunction "1_1") (pintype "passive"))
      (node (ref "SW15") (pin "3") (pinfunction "3_3") (pintype "passive"))
      (node (ref "SW15") (pin "4") (pinfunction "4_4") (pintype "passive"))
    )
    (net (code "47") (name "Net-(R18-Pad1)") (class "Default")
      (node (ref "R18") (pin "1") (pinfunction "1_1") (pintype "passive"))
      (node (ref "SW16") (pin "3") (pinfunction "3_3") (pintype "passive"))
      (node (ref "SW16") (pin "4") (pinfunction "4_4") (pintype "passive"))
    )
    (net (code "48") (name "OK") (class "Default")
      (node (ref "C12") (pin "1") (pinfunction "1_1") (pintype "passive"))
      (node (ref "IC1") (pin "15") (pinfunction "PB1_15") (pintype "bidirectional"))
      (node (ref "R10") (pin "2") (pinfunction "2_2") (pintype "passive"))
    )
    (net (code "49") (name "PWM") (class "Default")
      (node (ref "IC1") (pin "25") (pinfunction "PA15_25") (pintype "bidirectional"))
      (node (ref "R25") (pin "1") (pinfunction "1_1") (pintype "passive"))
      (node (ref "R26") (pin "1") (pinfunction "1_1") (pintype "passive"))
    )
    (net (code "50") (name "PWR") (class "Default")
      (node (ref "C5") (pin "1") (pinfunction "1_1") (pintype "passive"))
      (node (ref "IC1") (pin "8") (pinfunction "PA2_8") (pintype "bidirectional"))
      (node (ref "R3") (pin "2") (pinfunction "2_2") (pintype "passive"))
    )
    (net (code "51") (name "RGT") (class "Default")
      (node (ref "C9") (pin "1") (pinfunction "1_1") (pintype "passive"))
      (node (ref "IC1") (pin "12") (pinfunction "PA6_12") (pintype "bidirectional"))
      (node (ref "R7") (pin "2") (pinfunction "2_2") (pintype "passive"))
    )
    (net (code "52") (name "RX") (class "Default")
      (node (ref "IC1") (pin "30") (pinfunction "PB7_30") (pintype "bidirectional"))
      (node (ref "SV1") (pin "1") (pinfunction "1_1") (pintype "passive"))
    )
    (net (code "53") (name "SWCLK") (class "Default")
      (node (ref "IC1") (pin "24") (pinfunction "PA14_24") (pintype "bidirectional"))
      (node (ref "J2") (pin "4") (pinfunction "4_4") (pintype "passive"))
    )
    (net (code "54") (name "SWDIO") (class "Default")
      (node (ref "IC1") (pin "23") (pinfunction "PA13_23") (pintype "bidirectional"))
      (node (ref "J2") (pin "2") (pinfunction "2_2") (pintype "passive"))
    )
    (net (code "55") (name "TX") (class "Default")
      (node (ref "IC1") (pin "29") (pinfunction "PB6_29") (pintype "bidirectional"))
      (node (ref "SV1") (pin "2") (pinfunction "2_2") (pintype "passive"))
    )
    (net (code "56") (name "UP") (class "Default")
      (node (ref "C8") (pin "1") (pinfunction "1_1") (pintype "passive"))
      (node (ref "IC1") (pin "11") (pinfunction "PA5_11") (pintype "bidirectional"))
      (node (ref "R6") (pin "2") (pinfunction "2_2") (pintype "passive"))
    )
    (net (code "57") (name "USB_N") (class "Default")
      (node (ref "IC1") (pin "21") (pinfunction "PA11_21") (pintype "bidirectional"))
      (node (ref "R19") (pin "1") (pinfunction "1_1") (pintype "passive"))
    )
    (net (code "58") (name "USB_P") (class "Default")
      (node (ref "IC1") (pin "22") (pinfunction "PA12_22") (pintype "bidirectional"))
      (node (ref "R20") (pin "1") (pinfunction "1_1") (pintype "passive"))
    )
    (net (code "59") (name "V+") (class "Default")
      (node (ref "C23") (pin "1") (pinfunction "1_1") (pintype "passive"))
      (node (ref "IC4") (pin "3") (pinfunction "VBAT_3") (pintype "output"))
      (node (ref "IC5") (pin "1") (pinfunction "IN_1") (pintype "input"))
      (node (ref "IC5") (pin "3") (pinfunction "EN_3") (pintype "passive"))
      (node (ref "J1") (pin "1") (pinfunction "1_1") (pintype "passive"))
      (node (ref "R22") (pin "1") (pinfunction "1_1") (pintype "passive"))
      (node (ref "R28") (pin "1") (pinfunction "1_1") (pintype "passive"))
      (node (ref "R30") (pin "1") (pinfunction "1_1") (pintype "passive"))
    )
    (net (code "60") (name "V-") (class "Default")
      (node (ref "C25") (pin "2") (pinfunction "2_2") (pintype "passive"))
      (node (ref "IC6") (pin "1") (pinfunction "VSS_1") (pintype "input"))
      (node (ref "IC7") (pin "S") (pinfunction "S_S") (pintype "passive"))
      (node (ref "J1") (pin "2") (pinfunction "2_2") (pintype "passive"))
      (node (ref "J1") (pin "S1") (pinfunction "SHIELD_S1") (pintype "passive"))
      (node (ref "J1") (pin "S2") (pinfunction "SHIELD_S2") (pintype "passive"))
    )
    (net (code "61") (name "VBUS_SENSE") (class "Default")
      (node (ref "IC1") (pin "27") (pinfunction "PB4_27") (pintype "bidirectional"))
      (node (ref "R21") (pin "2") (pinfunction "2_2") (pintype "passive"))
      (node (ref "R29") (pin "1") (pinfunction "1_1") (pintype "passive"))
    )
    (net (code "62") (name "VOL+") (class "Default")
      (node (ref "C13") (pin "1") (pinfunction "1_1") (pintype "passive"))
      (node (ref "IC1") (pin "18") (pinfunction "PA8_18") (pintype "bidirectional"))
      (node (ref "R11") (pin "2") (pinfunction "2_2") (pintype "passive"))
    )
    (net (code "63") (name "VOL-") (class "Default")
      (node (ref "C14") (pin "1") (pinfunction "1_1") (pintype "passive"))
      (node (ref "IC1") (pin "19") (pinfunction "PA9_19") (pintype "bidirectional"))
      (node (ref "R12") (pin "2") (pinfunction "2_2") (pintype "passive"))
    )
    (net (code "64") (name "unconnected-(IC6-NC-Pad4)") (class "Default")
      (node (ref "IC6") (pin "4") (pinfunction "NC_4") (pintype "no_connect"))
    )
    (net (code "65") (name "unconnected-(J2-Pad6)") (class "Default")
      (node (ref "J2") (pin "6") (pinfunction "6_6") (pintype "passive"))
    )
    (net (code "66") (name "unconnected-(J2-Pad7)") (class "Default")
      (node (ref "J2") (pin "7") (pinfunction "7_7") (pintype "passive"))
    )
    (net (code "67") (name "unconnected-(J2-Pad8)") (class "Default")
      (node (ref "J2") (pin "8") (pinfunction "8_8") (pintype "passive"))
    )
    (net (code "68") (name "unconnected-(J3-ID-Pad4)") (class "Default")
      (node (ref "J3") (pin "4") (pinfunction "ID_4") (pintype "passive"))
    )
    (net (code "69") (name "~{NRST}") (class "Default")
      (node (ref "IC1") (pin "4") (pinfunction "~{NRST}_4") (pintype "input"))
      (node (ref "J2") (pin "10") (pinfunction "10_10") (pintype "passive"))
      (node (ref "R1") (pin "1") (pinfunction "1_1") (pintype "passive"))
    )
  )
)
